# LabAccessBoard.net
KiCad netlist of a schematic drawn in EAGLE
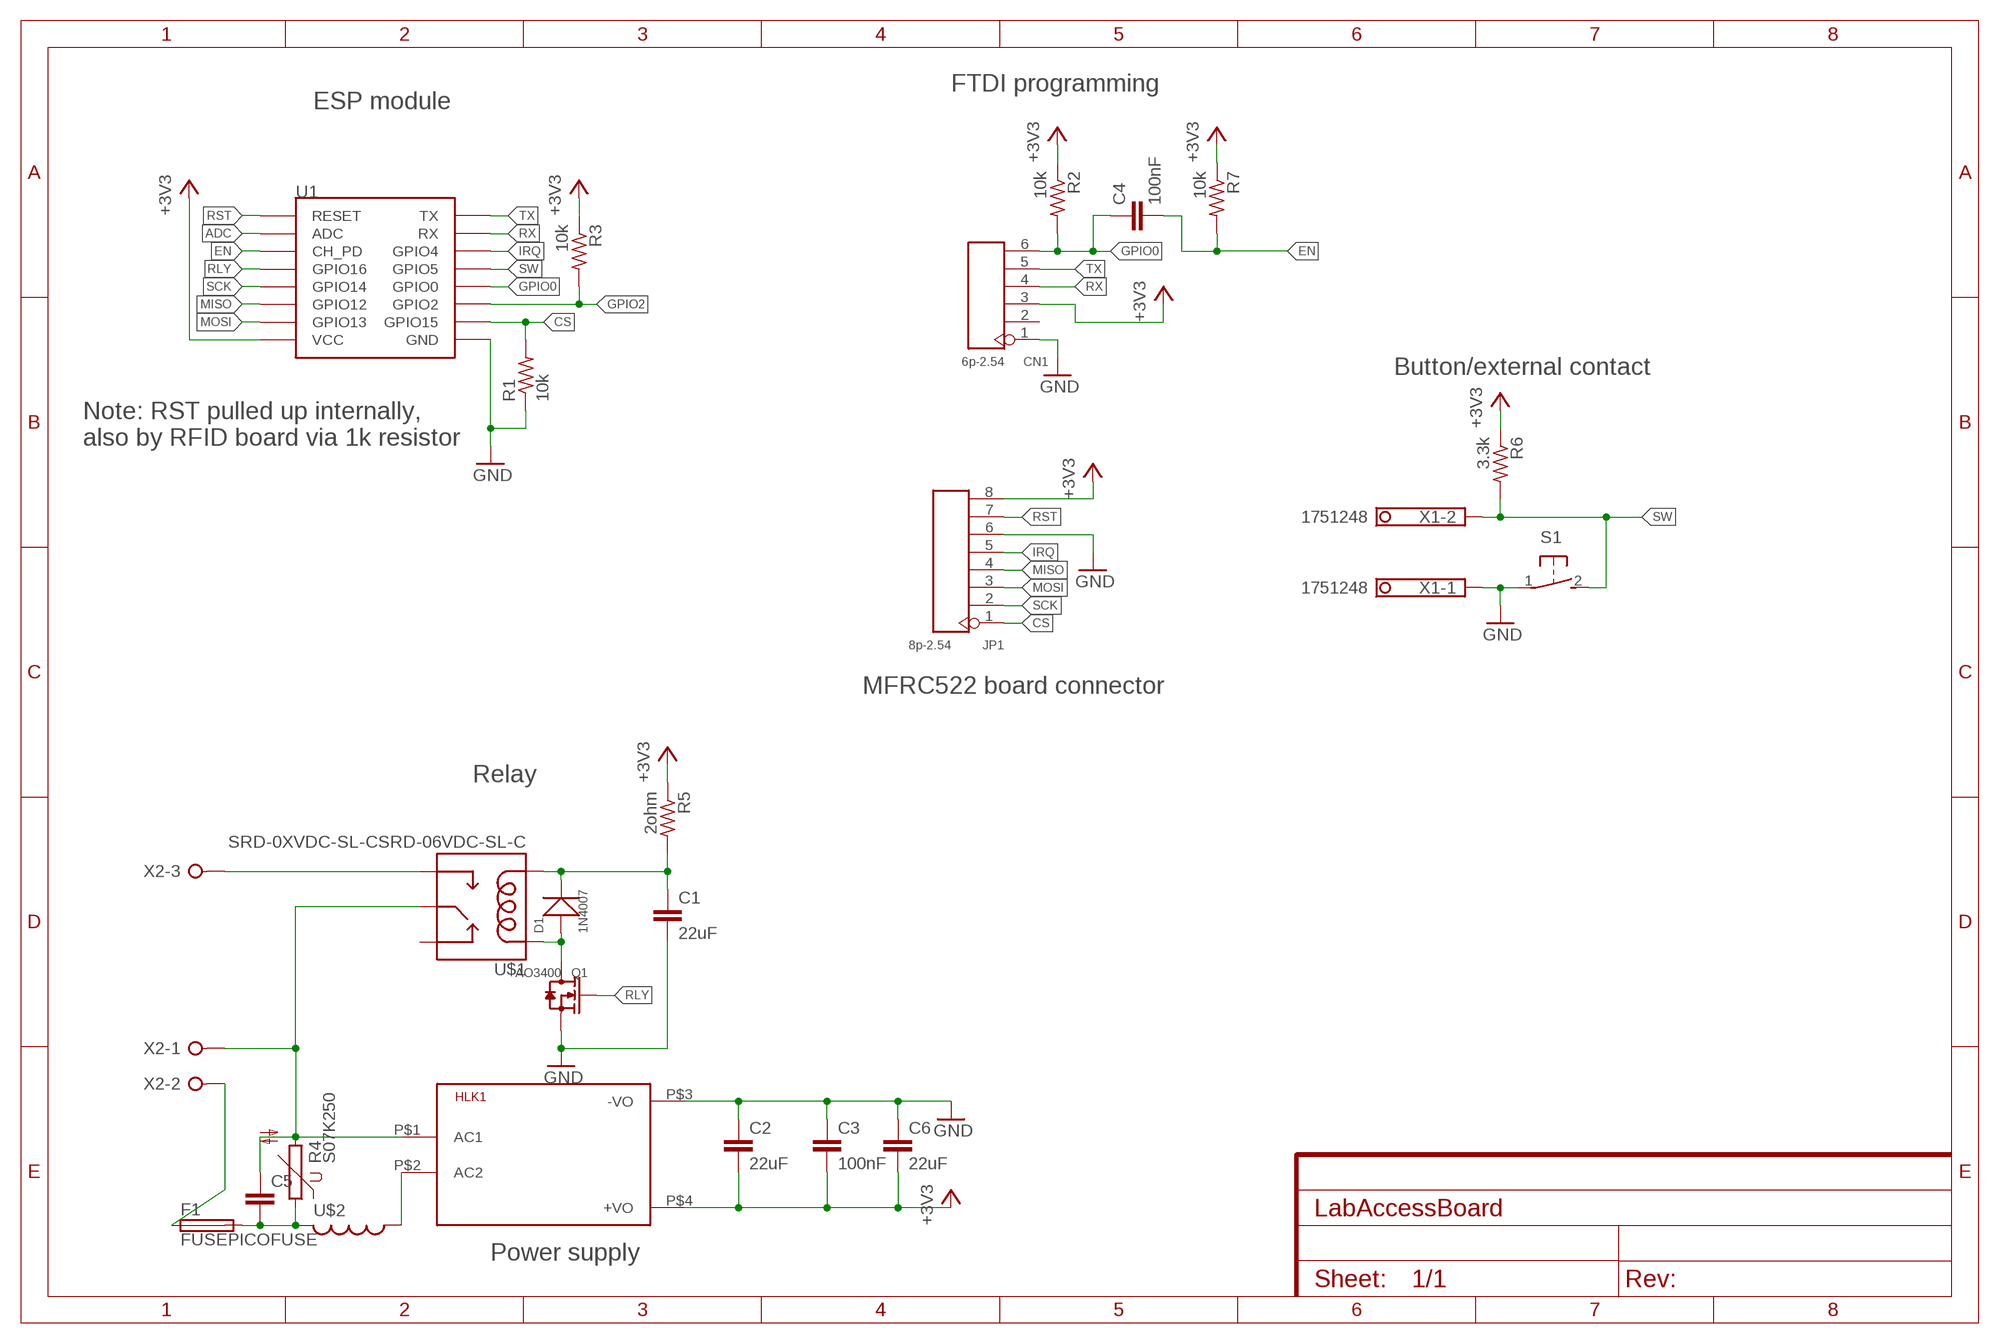
[diagram p0: schematic, sheet 1]

(export (version "E")
  (design (tool "Eeschema 10.0.6"))
  (components
    (comp (ref "C1")
      (value "22uF")
      (footprint "eagle-import:C0805K")
      (libsource (lib "eagle-import") (part "C-EUC0805K"))
    )
    (comp (ref "C2")
      (value "22uF")
      (footprint "eagle-import:C0805K")
      (libsource (lib "eagle-import") (part "C-EUC0805K"))
    )
    (comp (ref "C3")
      (value "100nF")
      (footprint "eagle-import:C0603K")
      (libsource (lib "eagle-import") (part "C-EUC0603K"))
    )
    (comp (ref "C4")
      (value "100nF")
      (footprint "eagle-import:C0603K")
      (libsource (lib "eagle-import") (part "C-EUC0603K"))
    )
    (comp (ref "C5")
      (value "C-EU102-064X133")
      (footprint "eagle-import:C102-064X133")
      (libsource (lib "eagle-import") (part "C-EU102-064X133"))
    )
    (comp (ref "C6")
      (value "22uF")
      (footprint "eagle-import:C0805K")
      (libsource (lib "eagle-import") (part "C-EUC0805K"))
    )
    (comp (ref "CN1")
      (value "6p-2.54")
      (footprint "eagle-import:H6-2.54")
      (fields (field (name "MPN") "F185-1106A1BSYC1"))
      (libsource (lib "eagle-import") (part "DIP-BLACK-FEMALE-HEADER-VERT(6P-2.54)"))
    )
    (comp (ref "D1")
      (value "1N4007")
      (footprint "eagle-import:DO-214AC")
      (libsource (lib "eagle-import") (part "DIODE-GEN-PURPOSE-1KV-1A(DO-214AC)"))
    )
    (comp (ref "F1")
      (value "FUSEPICOFUSE")
      (footprint "eagle-import:PICOFUSE")
      (libsource (lib "eagle-import") (part "FUSEPICOFUSE"))
    )
    (comp (ref "HLK1")
      (value "HLK-PM013W")
      (footprint "eagle-import:HLK-PM01")
      (libsource (lib "eagle-import") (part "HLK-PM013W"))
    )
    (comp (ref "JP1")
      (value "8p-2.54")
      (footprint "eagle-import:H8-2.54")
      (fields (field (name "MPN") "P125-1108A1BS116A1"))
      (libsource (lib "eagle-import") (part "DIP-BLACK-MALE-HEADER-VERT(8P-2.54)"))
    )
    (comp (ref "Q1")
      (value "AO3400")
      (footprint "eagle-import:SOT-23")
      (fields (field (name "MPN") "2N7002,215"))
      (libsource (lib "eagle-import") (part "SMD-MOSFET-N-CH-60V-300MA-LOGIC-LEVEL-FET-2N7002(SOT-23)"))
    )
    (comp (ref "R1")
      (value "10k")
      (footprint "eagle-import:R0603")
      (libsource (lib "eagle-import") (part "R-US_R0603"))
    )
    (comp (ref "R2")
      (value "10k")
      (footprint "eagle-import:R0603")
      (libsource (lib "eagle-import") (part "R-US_R0603"))
    )
    (comp (ref "R3")
      (value "10k")
      (footprint "eagle-import:R0603")
      (libsource (lib "eagle-import") (part "R-US_R0603"))
    )
    (comp (ref "R4")
      (value "S07K250")
      (footprint "eagle-import:S07K250")
      (libsource (lib "eagle-import") (part "S07K250"))
    )
    (comp (ref "R5")
      (value "2ohm")
      (footprint "eagle-import:R0603")
      (libsource (lib "eagle-import") (part "R-US_R0603"))
    )
    (comp (ref "R6")
      (value "3.3k")
      (footprint "eagle-import:R0603")
      (libsource (lib "eagle-import") (part "R-US_R0603"))
    )
    (comp (ref "R7")
      (value "10k")
      (footprint "eagle-import:R0603")
      (libsource (lib "eagle-import") (part "R-US_R0603"))
    )
    (comp (ref "S1")
      (value "31-XX")
      (footprint "eagle-import:B3F-31XX")
      (fields (field (name "MPN") "B3F-3100"))
      (libsource (lib "eagle-import") (part "31-XX"))
    )
    (comp (ref "U$1")
      (value "SRD-0XVDC-SL-CSRD-06VDC-SL-C")
      (footprint "eagle-import:SRD-0XVDC-SL-C")
      (libsource (lib "eagle-import") (part "SRD-0XVDC-SL-CSRD-06VDC-SL-C"))
    )
    (comp (ref "U$2")
      (value "L-US6000-XXX-RC")
      (footprint "eagle-import:6000-XXXX-RC")
      (libsource (lib "eagle-import") (part "L-US6000-XXX-RC"))
    )
    (comp (ref "U1")
      (value "ESP12SMD")
      (footprint "eagle-import:ESP12-SMD")
      (libsource (lib "eagle-import") (part "ESP12SMD"))
    )
    (comp (ref "X1")
      (value "1751248")
      (footprint "eagle-import:1751248")
      (libsource (lib "eagle-import") (part "1751248"))
    )
    (comp (ref "X2")
      (value "W237-3E")
      (footprint "eagle-import:W237-3E")
      (libsource (lib "eagle-import") (part "W237-3E"))
    )
  )
  (nets
    (net (code "1") (name "+3V3") (class "Default")
      (node (ref "C2") (pin "2") (pinfunction "2_2") (pintype "passive"))
      (node (ref "C3") (pin "2") (pinfunction "2_2") (pintype "passive"))
      (node (ref "C6") (pin "2") (pinfunction "2_2") (pintype "passive"))
      (node (ref "CN1") (pin "3") (pinfunction "3_3") (pintype "bidirectional"))
      (node (ref "HLK1") (pin "P$4") (pinfunction "+VO_P$4") (pintype "bidirectional"))
      (node (ref "JP1") (pin "8") (pinfunction "8_8") (pintype "bidirectional"))
      (node (ref "R2") (pin "1") (pinfunction "1_1") (pintype "passive"))
      (node (ref "R3") (pin "1") (pinfunction "1_1") (pintype "passive"))
      (node (ref "R5") (pin "1") (pinfunction "1_1") (pintype "passive"))
      (node (ref "R6") (pin "1") (pinfunction "1_1") (pintype "passive"))
      (node (ref "R7") (pin "1") (pinfunction "1_1") (pintype "passive"))
      (node (ref "U1") (pin "VCC") (pinfunction "VCC_VCC") (pintype "bidirectional"))
    )
    (net (code "2") (name "ADC") (class "Default")
      (node (ref "U1") (pin "ADC") (pinfunction "ADC_ADC") (pintype "bidirectional"))
    )
    (net (code "3") (name "CS") (class "Default")
      (node (ref "JP1") (pin "1") (pinfunction "1_1") (pintype "bidirectional"))
      (node (ref "R1") (pin "2") (pinfunction "2_2") (pintype "passive"))
      (node (ref "U1") (pin "GPIO15") (pinfunction "GPIO15_GPIO15") (pintype "bidirectional"))
    )
    (net (code "4") (name "EN") (class "Default")
      (node (ref "C4") (pin "2") (pinfunction "2_2") (pintype "passive"))
      (node (ref "R7") (pin "2") (pinfunction "2_2") (pintype "passive"))
      (node (ref "U1") (pin "CH_PD") (pinfunction "CH_PD_CH_PD") (pintype "bidirectional"))
    )
    (net (code "5") (name "GND") (class "Default")
      (node (ref "C1") (pin "2") (pinfunction "2_2") (pintype "passive"))
      (node (ref "C2") (pin "1") (pinfunction "1_1") (pintype "passive"))
      (node (ref "C3") (pin "1") (pinfunction "1_1") (pintype "passive"))
      (node (ref "C6") (pin "1") (pinfunction "1_1") (pintype "passive"))
      (node (ref "CN1") (pin "1") (pinfunction "1_1") (pintype "bidirectional"))
      (node (ref "HLK1") (pin "P$3") (pinfunction "-VO_P$3") (pintype "bidirectional"))
      (node (ref "JP1") (pin "6") (pinfunction "6_6") (pintype "bidirectional"))
      (node (ref "Q1") (pin "2") (pinfunction "S_2") (pintype "passive"))
      (node (ref "R1") (pin "1") (pinfunction "1_1") (pintype "passive"))
      (node (ref "S1") (pin "1") (pinfunction "P_1") (pintype "passive"))
      (node (ref "U1") (pin "GND") (pinfunction "GND_GND") (pintype "bidirectional"))
      (node (ref "X1") (pin "1") (pinfunction "K_1") (pintype "passive"))
    )
    (net (code "6") (name "GPIO0") (class "Default")
      (node (ref "C4") (pin "1") (pinfunction "1_1") (pintype "passive"))
      (node (ref "CN1") (pin "6") (pinfunction "6_6") (pintype "bidirectional"))
      (node (ref "R2") (pin "2") (pinfunction "2_2") (pintype "passive"))
      (node (ref "U1") (pin "GPIO0") (pinfunction "GPIO0_GPIO0") (pintype "bidirectional"))
    )
    (net (code "7") (name "GPIO2") (class "Default")
      (node (ref "R3") (pin "2") (pinfunction "2_2") (pintype "passive"))
      (node (ref "U1") (pin "GPIO2") (pinfunction "GPIO2_GPIO2") (pintype "bidirectional"))
    )
    (net (code "8") (name "IRQ") (class "Default")
      (node (ref "JP1") (pin "5") (pinfunction "5_5") (pintype "bidirectional"))
      (node (ref "U1") (pin "GPIO4") (pinfunction "GPIO4_GPIO4") (pintype "bidirectional"))
    )
    (net (code "9") (name "MISO") (class "Default")
      (node (ref "JP1") (pin "4") (pinfunction "4_4") (pintype "bidirectional"))
      (node (ref "U1") (pin "GPIO12") (pinfunction "GPIO12_GPIO12") (pintype "bidirectional"))
    )
    (net (code "10") (name "MOSI") (class "Default")
      (node (ref "JP1") (pin "3") (pinfunction "3_3") (pintype "bidirectional"))
      (node (ref "U1") (pin "GPIO13") (pinfunction "GPIO13_GPIO13") (pintype "bidirectional"))
    )
    (net (code "11") (name "Net-(C5-Pad2)") (class "Default")
      (node (ref "C5") (pin "2") (pinfunction "2_2") (pintype "passive"))
      (node (ref "F1") (pin "2") (pinfunction "2_2") (pintype "passive"))
      (node (ref "R4") (pin "1") (pinfunction "1_1") (pintype "passive"))
      (node (ref "U$2") (pin "2") (pinfunction "2_2") (pintype "passive"))
    )
    (net (code "12") (name "Net-(D1-+)") (class "Default")
      (node (ref "D1") (pin "1") (pinfunction "+_1") (pintype "passive"))
      (node (ref "Q1") (pin "3") (pinfunction "D_3") (pintype "passive"))
      (node (ref "U$1") (pin "COIL1") (pinfunction "COIL1_COIL1") (pintype "bidirectional"))
    )
    (net (code "13") (name "Net-(D1--)") (class "Default")
      (node (ref "C1") (pin "1") (pinfunction "1_1") (pintype "passive"))
      (node (ref "D1") (pin "2") (pinfunction "-_2") (pintype "passive"))
      (node (ref "R5") (pin "2") (pinfunction "2_2") (pintype "passive"))
      (node (ref "U$1") (pin "COIL0") (pinfunction "COIL0_COIL0") (pintype "bidirectional"))
    )
    (net (code "14") (name "Net-(HLK1-AC1)") (class "Default")
      (node (ref "C5") (pin "1") (pinfunction "1_1") (pintype "passive"))
      (node (ref "HLK1") (pin "P$1") (pinfunction "AC1_P$1") (pintype "bidirectional"))
      (node (ref "R4") (pin "2") (pinfunction "2_2") (pintype "passive"))
      (node (ref "U$1") (pin "SWCOMMON") (pinfunction "SWCOMMON_SWCOMMON") (pintype "bidirectional"))
      (node (ref "X2") (pin "1") (pinfunction "KL_1") (pintype "passive"))
    )
    (net (code "15") (name "Net-(HLK1-AC2)") (class "Default")
      (node (ref "HLK1") (pin "P$2") (pinfunction "AC2_P$2") (pintype "bidirectional"))
      (node (ref "U$2") (pin "1") (pinfunction "1_1") (pintype "passive"))
    )
    (net (code "16") (name "Net-(X2B-KL)") (class "Default")
      (node (ref "F1") (pin "1") (pinfunction "1_1") (pintype "passive"))
      (node (ref "X2") (pin "2") (pinfunction "KL_2") (pintype "passive"))
    )
    (net (code "17") (name "Net-(X2C-KL)") (class "Default")
      (node (ref "U$1") (pin "SWOPEN") (pinfunction "SWOPEN_SWOPEN") (pintype "bidirectional"))
      (node (ref "X2") (pin "3") (pinfunction "KL_3") (pintype "passive"))
    )
    (net (code "18") (name "RLY") (class "Default")
      (node (ref "Q1") (pin "1") (pinfunction "G_1") (pintype "passive"))
      (node (ref "U1") (pin "GPIO16") (pinfunction "GPIO16_GPIO16") (pintype "bidirectional"))
    )
    (net (code "19") (name "RST") (class "Default")
      (node (ref "JP1") (pin "7") (pinfunction "7_7") (pintype "bidirectional"))
      (node (ref "U1") (pin "RESET") (pinfunction "RESET_RESET") (pintype "bidirectional"))
    )
    (net (code "20") (name "RX") (class "Default")
      (node (ref "CN1") (pin "4") (pinfunction "4_4") (pintype "bidirectional"))
      (node (ref "U1") (pin "RXD0") (pinfunction "RX_RXD0") (pintype "bidirectional"))
    )
    (net (code "21") (name "SCK") (class "Default")
      (node (ref "JP1") (pin "2") (pinfunction "2_2") (pintype "bidirectional"))
      (node (ref "U1") (pin "GPIO14") (pinfunction "GPIO14_GPIO14") (pintype "bidirectional"))
    )
    (net (code "22") (name "SW") (class "Default")
      (node (ref "R6") (pin "2") (pinfunction "2_2") (pintype "passive"))
      (node (ref "S1") (pin "2") (pinfunction "S_2") (pintype "passive"))
      (node (ref "U1") (pin "GPIO5") (pinfunction "GPIO5_GPIO5") (pintype "bidirectional"))
      (node (ref "X1") (pin "2") (pinfunction "K_2") (pintype "passive"))
    )
    (net (code "23") (name "TX") (class "Default")
      (node (ref "CN1") (pin "5") (pinfunction "5_5") (pintype "bidirectional"))
      (node (ref "U1") (pin "TXD0") (pinfunction "TX_TXD0") (pintype "bidirectional"))
    )
    (net (code "24") (name "unconnected-(CN1-Pad2)") (class "Default")
      (node (ref "CN1") (pin "2") (pinfunction "2_2") (pintype "bidirectional"))
    )
    (net (code "25") (name "unconnected-(U$1-SWCLOSE-PadSWCLOSED)") (class "Default")
      (node (ref "U$1") (pin "SWCLOSED") (pinfunction "SWCLOSE_SWCLOSED") (pintype "bidirectional"))
    )
  )
)
